# ETAG_v10_0_EM4095.net
KiCad netlist of a schematic drawn in EAGLE
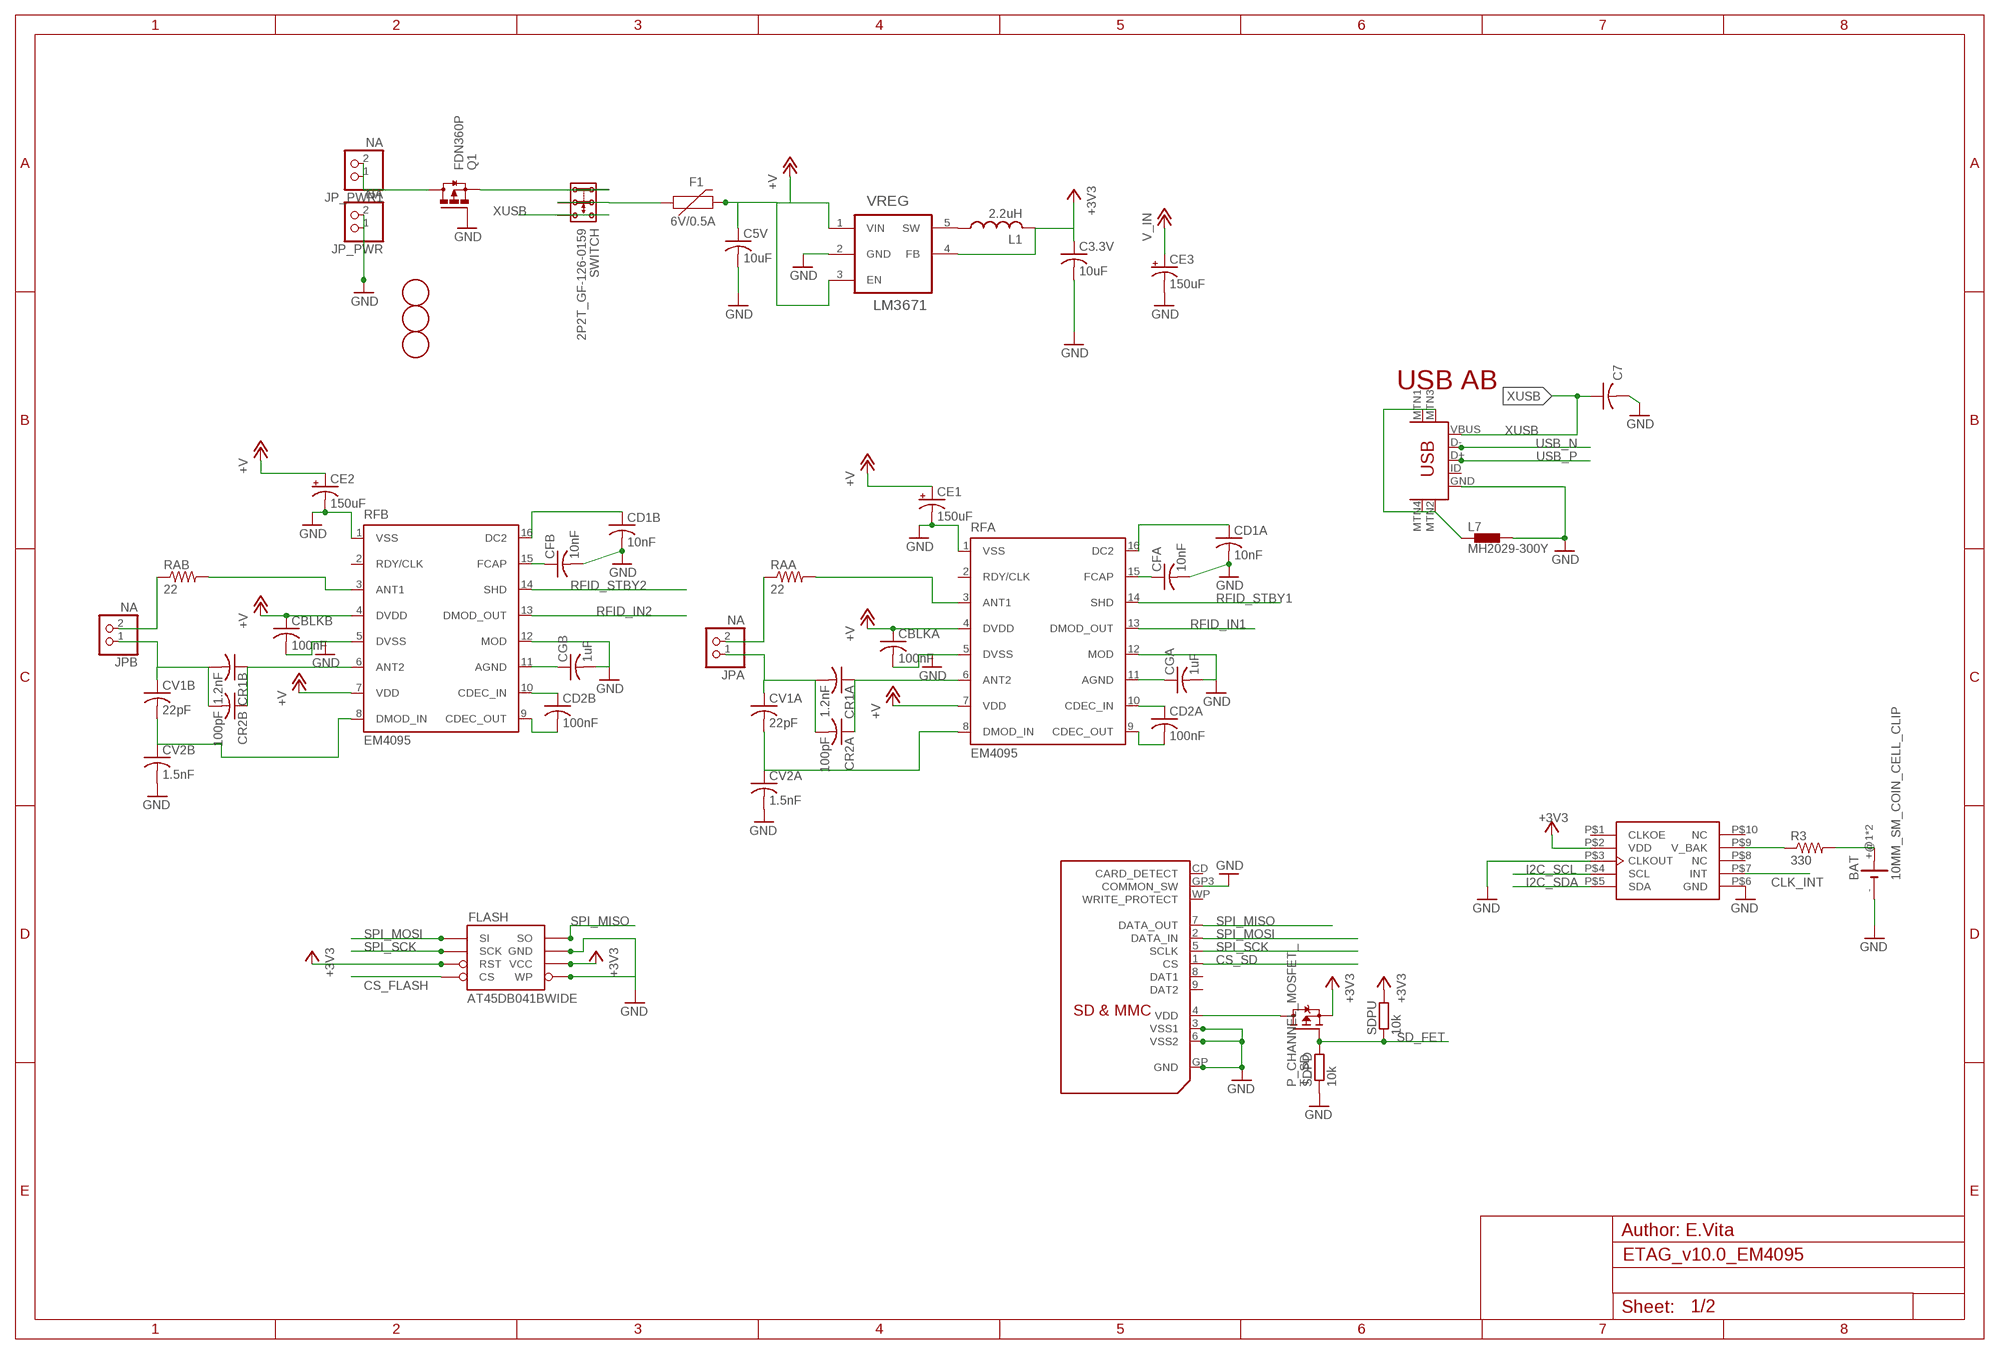
[diagram p0: schematic, sheet 1]
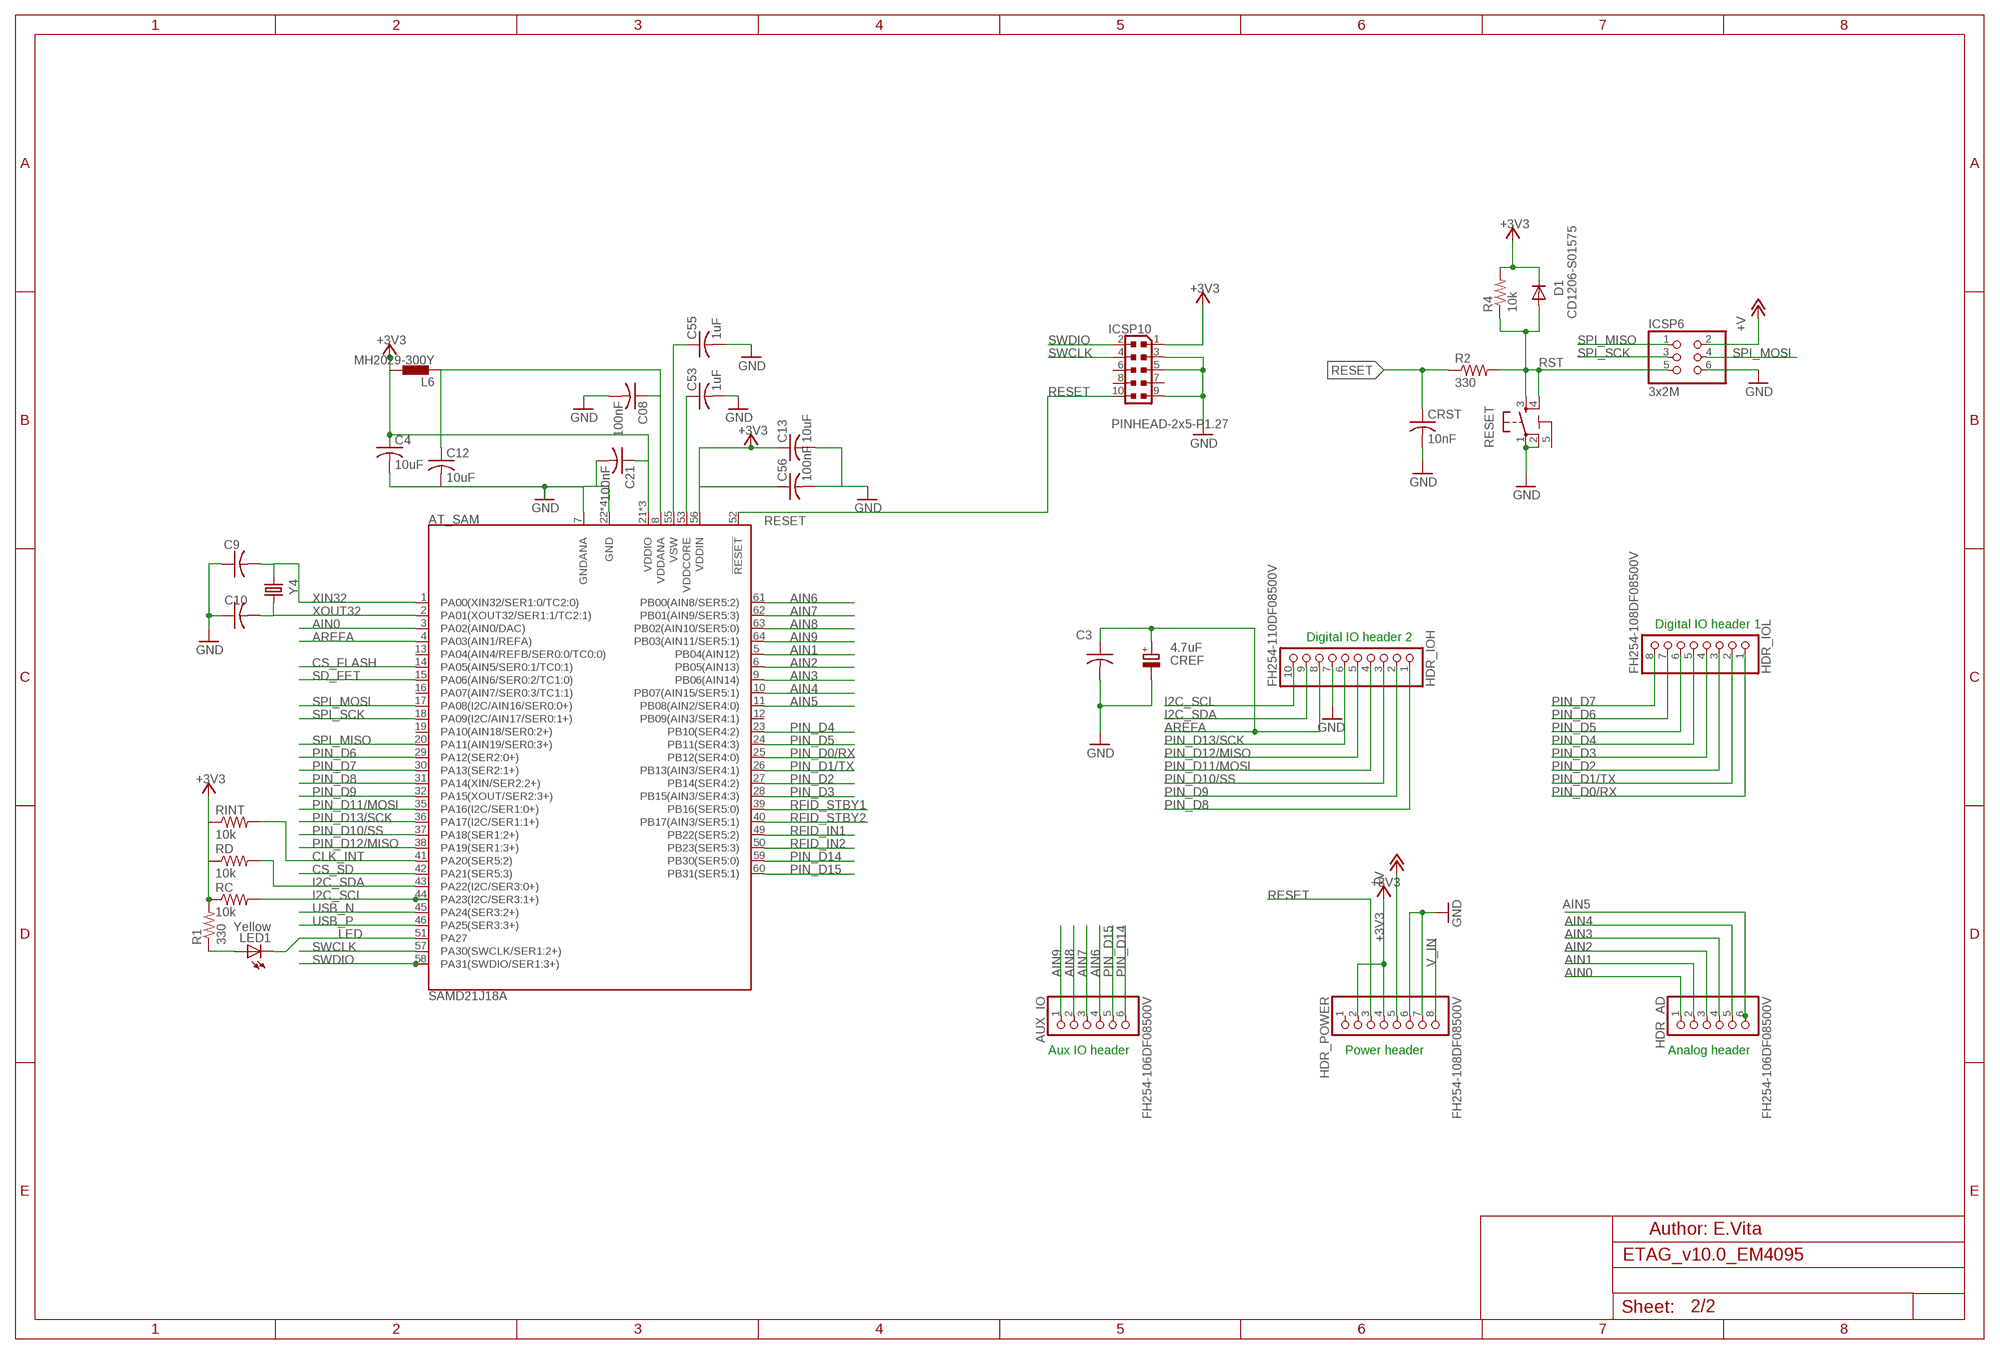
[diagram p1: schematic, sheet 2]

(export (version "E")
  (design (tool "Eeschema 10.0.6"))
  (components
    (comp (ref "BAT")
      (value "10MM_SM_COIN_CELL_CLIP")
      (footprint "eagle-import:10MM_SM_COIN_CELL_CLIP")
      (libsource (lib "eagle-import") (part "10MM_SM_COIN_CELL_CLIP"))
    )
    (comp (ref "C3.3V")
      (value "10uF")
      (footprint "eagle-import:C0805")
      (libsource (lib "eagle-import") (part "C-USC0805"))
    )
    (comp (ref "C5V")
      (value "10uF")
      (footprint "eagle-import:C0805")
      (libsource (lib "eagle-import") (part "C-USC0805"))
    )
    (comp (ref "C7")
      (value "10nF")
      (footprint "eagle-import:C0603-ROUND")
      (libsource (lib "eagle-import") (part "C-USROUND"))
    )
    (comp (ref "CBLKA")
      (value "100nF")
      (footprint "eagle-import:C0603-ROUND")
      (libsource (lib "eagle-import") (part "C-US"))
    )
    (comp (ref "CBLKB")
      (value "100nF")
      (footprint "eagle-import:C0603-ROUND")
      (libsource (lib "eagle-import") (part "C-US"))
    )
    (comp (ref "CD1A")
      (value "10nF")
      (footprint "eagle-import:C0603-ROUND")
      (libsource (lib "eagle-import") (part "C-US"))
    )
    (comp (ref "CD1B")
      (value "10nF")
      (footprint "eagle-import:C0603-ROUND")
      (libsource (lib "eagle-import") (part "C-USROUND"))
    )
    (comp (ref "CD2A")
      (value "100nF")
      (footprint "eagle-import:C0603-ROUND")
      (libsource (lib "eagle-import") (part "C-US"))
    )
    (comp (ref "CD2B")
      (value "100nF")
      (footprint "eagle-import:C0603-ROUND")
      (libsource (lib "eagle-import") (part "C-US"))
    )
    (comp (ref "CE1")
      (value "150uF")
      (footprint "eagle-import:E2-5")
      (libsource (lib "eagle-import") (part "CPOL-USE2-5"))
    )
    (comp (ref "CE2")
      (value "150uF")
      (footprint "eagle-import:E2-5")
      (libsource (lib "eagle-import") (part "CPOL-USE2-5"))
    )
    (comp (ref "CE3")
      (value "150uF")
      (footprint "eagle-import:E2-5")
      (libsource (lib "eagle-import") (part "CPOL-USE2-5"))
    )
    (comp (ref "CFA")
      (value "10nF")
      (footprint "eagle-import:C0603-ROUND")
      (libsource (lib "eagle-import") (part "C-USROUND"))
    )
    (comp (ref "CFB")
      (value "10nF")
      (footprint "eagle-import:C0603-ROUND")
      (libsource (lib "eagle-import") (part "C-US"))
    )
    (comp (ref "CGA")
      (value "1uF")
      (footprint "eagle-import:C0603-ROUND")
      (libsource (lib "eagle-import") (part "C-US"))
    )
    (comp (ref "CGB")
      (value "1uF")
      (footprint "eagle-import:C0603-ROUND")
      (libsource (lib "eagle-import") (part "C-US"))
    )
    (comp (ref "CR1A")
      (value "1.2nF")
      (footprint "eagle-import:C0603-ROUND")
      (libsource (lib "eagle-import") (part "C-USROUND"))
    )
    (comp (ref "CR1B")
      (value "1.2nF")
      (footprint "eagle-import:C0603-ROUND")
      (libsource (lib "eagle-import") (part "C-US"))
    )
    (comp (ref "CR2A")
      (value "100pF")
      (footprint "eagle-import:C0603-ROUND")
      (libsource (lib "eagle-import") (part "C-US"))
    )
    (comp (ref "CR2B")
      (value "100pF")
      (footprint "eagle-import:C0603-ROUND")
      (libsource (lib "eagle-import") (part "C-US"))
    )
    (comp (ref "CV1A")
      (value "22pF")
      (footprint "eagle-import:C0603-ROUND")
      (libsource (lib "eagle-import") (part "C-US"))
    )
    (comp (ref "CV1B")
      (value "22pF")
      (footprint "eagle-import:C0603-ROUND")
      (libsource (lib "eagle-import") (part "C-US"))
    )
    (comp (ref "CV2A")
      (value "1.5nF")
      (footprint "eagle-import:C0603-ROUND")
      (libsource (lib "eagle-import") (part "C-USROUND"))
    )
    (comp (ref "CV2B")
      (value "1.5nF")
      (footprint "eagle-import:C0603-ROUND")
      (libsource (lib "eagle-import") (part "C-US"))
    )
    (comp (ref "F1")
      (value "6V/0.5A")
      (footprint "eagle-import:1206")
      (libsource (lib "eagle-import") (part "PPTC_6V500MA-2"))
    )
    (comp (ref "FD1")
      (value "FIDUCIALMOUNT")
      (footprint "eagle-import:FIDUCIA-MOUNT")
      (libsource (lib "eagle-import") (part "FIDUCIALMOUNT"))
    )
    (comp (ref "FD2")
      (value "FIDUCIALMOUNT")
      (footprint "eagle-import:FIDUCIA-MOUNT")
      (libsource (lib "eagle-import") (part "FIDUCIALMOUNT"))
    )
    (comp (ref "FD3")
      (value "FIDUCIALMOUNT")
      (footprint "eagle-import:FIDUCIA-MOUNT")
      (libsource (lib "eagle-import") (part "FIDUCIALMOUNT"))
    )
    (comp (ref "FLASH")
      (value "AT45DB041BWIDE")
      (footprint "eagle-import:SO08WIDE")
      (libsource (lib "eagle-import") (part "AT45DB041BWIDE"))
    )
    (comp (ref "JPA")
      (value "NA")
      (footprint "eagle-import:1X02")
      (libsource (lib "eagle-import") (part "PINHD-1X2"))
    )
    (comp (ref "JPB")
      (value "NA")
      (footprint "eagle-import:1X02")
      (libsource (lib "eagle-import") (part "PINHD-1X2"))
    )
    (comp (ref "JP_PWR")
      (value "NA")
      (footprint "eagle-import:1X02")
      (libsource (lib "eagle-import") (part "PINHD-1X2"))
    )
    (comp (ref "JP_PWR1")
      (value "NA")
      (footprint "eagle-import:1X02")
      (libsource (lib "eagle-import") (part "PINHD-1X2"))
    )
    (comp (ref "L1")
      (value "2.2uH")
      (footprint "eagle-import:SMT_COIL_INDUCTOR_4X4MM")
      (libsource (lib "eagle-import") (part "L-US4X4"))
    )
    (comp (ref "L7")
      (value "MH2029-300Y")
      (footprint "eagle-import:C0805K")
      (libsource (lib "eagle-import") (part "BLM15H0805"))
    )
    (comp (ref "Q1")
      (value "FDN360P")
      (footprint "eagle-import:SUPER-SOT3")
      (libsource (lib "eagle-import") (part "FDN360P"))
    )
    (comp (ref "R3")
      (value "330")
      (footprint "eagle-import:C0603-ROUND")
      (libsource (lib "eagle-import") (part "R-US_ROUND"))
    )
    (comp (ref "RAA")
      (value "22")
      (footprint "eagle-import:R0805")
      (libsource (lib "eagle-import") (part "R-US_R0805"))
    )
    (comp (ref "RAB")
      (value "22")
      (footprint "eagle-import:R0805")
      (libsource (lib "eagle-import") (part "R-US_R0805"))
    )
    (comp (ref "RFA")
      (value "EM4095")
      (footprint "eagle-import:SO16")
      (libsource (lib "eagle-import") (part "EM4095"))
    )
    (comp (ref "RFB")
      (value "EM4095")
      (footprint "eagle-import:SO16")
      (libsource (lib "eagle-import") (part "EM4095"))
    )
    (comp (ref "RTC")
      (value "MC-RTC-RV-3029-C3-I2C")
      (footprint "eagle-import:MC-RTC-C3_SPECIAL")
      (libsource (lib "eagle-import") (part "MC-RTC-RV-3029-C3-I2C"))
    )
    (comp (ref "SD")
      (value "SDMMC06132")
      (footprint "eagle-import:06132")
      (libsource (lib "eagle-import") (part "SDMMC06132"))
    )
    (comp (ref "SDPD")
      (value "10k")
      (footprint "eagle-import:R0603-ROUND")
      (fields (field (name "PART_NUMBER") "CR0603JW103L"))
      (libsource (lib "eagle-import") (part "0028_CR0603JW103L"))
    )
    (comp (ref "SDPU")
      (value "10k")
      (footprint "eagle-import:R0603-ROUND")
      (fields (field (name "PART_NUMBER") "CR0603JW103L"))
      (libsource (lib "eagle-import") (part "0028_CR0603JW103L"))
    )
    (comp (ref "SWITCH")
      (value "2P2T_GF-126-0159")
      (footprint "eagle-import:2P2T_GF-126-0159")
      (libsource (lib "eagle-import") (part "2P2T_GF-126-0159"))
    )
    (comp (ref "T_SD")
      (value "P_CHANNEL_MOSFET_")
      (footprint "eagle-import:SOT23")
      (libsource (lib "eagle-import") (part "P_CHANNEL_MOSFET_"))
    )
    (comp (ref "USB")
      (value "USB-MINIB-5PIN")
      (footprint "eagle-import:USB-MINIB")
      (libsource (lib "eagle-import") (part "USB-MINIB-5PIN"))
    )
    (comp (ref "VREG")
      (value "LM3671")
      (footprint "eagle-import:SOT23-5L")
      (libsource (lib "eagle-import") (part "LM3671_SWITCHING_REGSOT23"))
    )
    (comp (ref "AT_SAM")
      (value "SAMD21J18A")
      (footprint "eagle-import:TQFP_10MM_0.5PITCH")
      (libsource (lib "eagle-import") (part "ATSAML21JTQFP_10MM_0.5PITCH"))
    )
    (comp (ref "AUX_IO")
      (value "FH254-106DF08500V")
      (footprint "eagle-import:1X06")
      (fields (field (name "PART_NUMBER") "20TW-535"))
      (libsource (lib "eagle-import") (part "1682_20TW-535_STD"))
    )
    (comp (ref "C3")
      (value "100nF")
      (footprint "eagle-import:C0603-ROUND")
      (libsource (lib "eagle-import") (part "C-USROUND"))
    )
    (comp (ref "C4")
      (value "10uF")
      (footprint "eagle-import:C0805")
      (libsource (lib "eagle-import") (part "C-USC0805"))
    )
    (comp (ref "C08")
      (value "100nF")
      (footprint "eagle-import:C0603-ROUND")
      (libsource (lib "eagle-import") (part "C-USROUND"))
    )
    (comp (ref "C9")
      (value "22pF")
      (footprint "eagle-import:C0603-ROUND")
      (libsource (lib "eagle-import") (part "C-USROUND"))
    )
    (comp (ref "C10")
      (value "22pF")
      (footprint "eagle-import:C0603-ROUND")
      (libsource (lib "eagle-import") (part "C-USROUND"))
    )
    (comp (ref "C12")
      (value "10uF")
      (footprint "eagle-import:C0805")
      (libsource (lib "eagle-import") (part "C-USC0805"))
    )
    (comp (ref "C13")
      (value "10uF")
      (footprint "eagle-import:C0805")
      (libsource (lib "eagle-import") (part "C-USC0805"))
    )
    (comp (ref "C21")
      (value "100nF")
      (footprint "eagle-import:C0603-ROUND")
      (libsource (lib "eagle-import") (part "C-USROUND"))
    )
    (comp (ref "C53")
      (value "1uF")
      (footprint "eagle-import:C0603-ROUND")
      (libsource (lib "eagle-import") (part "C-USROUND"))
    )
    (comp (ref "C55")
      (value "1uF")
      (footprint "eagle-import:C0603-ROUND")
      (libsource (lib "eagle-import") (part "C-USROUND"))
    )
    (comp (ref "C56")
      (value "100nF")
      (footprint "eagle-import:C0603-ROUND")
      (libsource (lib "eagle-import") (part "C-USROUND"))
    )
    (comp (ref "CREF")
      (value "4.7uF")
      (footprint "eagle-import:SMC_A")
      (fields (field (name "PART_NUMBER") "TAJA475M016RNJ"))
      (libsource (lib "eagle-import") (part "0474_TAJA475M016RNJ"))
    )
    (comp (ref "CRST")
      (value "10nF")
      (footprint "eagle-import:C0603-ROUND")
      (libsource (lib "eagle-import") (part "C-USROUND"))
    )
    (comp (ref "D1")
      (value "CD1206-S01575")
      (footprint "eagle-import:MINIMELF")
      (libsource (lib "eagle-import") (part "0012_CD1206-S01575"))
    )
    (comp (ref "HDR_AD")
      (value "FH254-106DF08500V")
      (footprint "eagle-import:1X06")
      (fields (field (name "PART_NUMBER") "20TW-535"))
      (libsource (lib "eagle-import") (part "1682_20TW-535_STD"))
    )
    (comp (ref "HDR_IOH")
      (value "FH254-110DF08500V")
      (footprint "eagle-import:1X10")
      (fields (field (name "PART_NUMBER") "20TW-537"))
      (libsource (lib "eagle-import") (part "1684_20TW-537"))
    )
    (comp (ref "HDR_IOL")
      (value "FH254-108DF08500V")
      (footprint "eagle-import:1X08")
      (fields (field (name "PART_NUMBER") "20TW-536"))
      (libsource (lib "eagle-import") (part "1683_20TW-536"))
    )
    (comp (ref "HDR_POWER")
      (value "FH254-108DF08500V")
      (footprint "eagle-import:1X08")
      (fields (field (name "PART_NUMBER") "20TW-536"))
      (libsource (lib "eagle-import") (part "1683_20TW-536"))
    )
    (comp (ref "ICSP6")
      (value "3x2M")
      (footprint "eagle-import:2X03")
      (fields (field (name "PART_NUMBER") "PH254-203DF118A00V"))
      (libsource (lib "eagle-import") (part "0114_PH254-203DF118A00V"))
    )
    (comp (ref "ICSP10")
      (value "PINHEAD-2x5-P1.27")
      (footprint "eagle-import:PINHEAD_2X05_127")
      (libsource (lib "eagle-import") (part "0171_PH127-205DF055G00AROUND-PADS"))
    )
    (comp (ref "L6")
      (value "MH2029-300Y")
      (footprint "eagle-import:C0805K")
      (libsource (lib "eagle-import") (part "BLM15H0805"))
    )
    (comp (ref "LED1")
      (value "Yellow")
      (footprint "eagle-import:CHIPLED_0805")
      (fields (field (name "PART_NUMBER") "KPT-2012YC"))
      (libsource (lib "eagle-import") (part "0044_KPT-2012YC"))
    )
    (comp (ref "R1")
      (value "330")
      (footprint "eagle-import:C0603-ROUND")
      (libsource (lib "eagle-import") (part "R-US_ROUND"))
    )
    (comp (ref "R2")
      (value "330")
      (footprint "eagle-import:C0603-ROUND")
      (libsource (lib "eagle-import") (part "R-US_ROUND"))
    )
    (comp (ref "R4")
      (value "10k")
      (footprint "eagle-import:C0603-ROUND")
      (libsource (lib "eagle-import") (part "R-US_ROUND"))
    )
    (comp (ref "RC")
      (value "10k")
      (footprint "eagle-import:C0603-ROUND")
      (libsource (lib "eagle-import") (part "R-US_ROUND"))
    )
    (comp (ref "RD")
      (value "10k")
      (footprint "eagle-import:C0603-ROUND")
      (libsource (lib "eagle-import") (part "R-US_ROUND"))
    )
    (comp (ref "RESET")
      (value "TS42031-160R-TR-7260")
      (footprint "eagle-import:TS42")
      (fields (field (name "PART_NUMBER") "IT-1157AHNP-160G-G_GTR"))
      (libsource (lib "eagle-import") (part "0946_TS42031-160W-TR-7260"))
    )
    (comp (ref "RINT")
      (value "10k")
      (footprint "eagle-import:C0603-ROUND")
      (libsource (lib "eagle-import") (part "R-US_ROUND"))
    )
    (comp (ref "Y4")
      (value "32,768Khz")
      (footprint "eagle-import:RESONATOR_EPSON_FC_145")
      (fields (field (name "PART_NUMBER") "ABS07-32.768KHZ-T"))
      (libsource (lib "eagle-import") (part "0213_ABS07-32.768KHZ-T"))
    )
  )
  (nets
    (net (code "1") (name "+3V3") (class "Default")
      (node (ref "AT_SAM") (pin "21") (pinfunction "VDDIO_21") (pintype "bidirectional"))
      (node (ref "AT_SAM") (pin "34") (pinfunction "VDDIO_34") (pintype "bidirectional"))
      (node (ref "AT_SAM") (pin "48") (pinfunction "VDDIO_48") (pintype "bidirectional"))
      (node (ref "AT_SAM") (pin "56") (pinfunction "VDDIN_56") (pintype "bidirectional"))
      (node (ref "C13") (pin "1") (pinfunction "1_1") (pintype "passive"))
      (node (ref "C21") (pin "1") (pinfunction "1_1") (pintype "passive"))
      (node (ref "C3.3V") (pin "1") (pinfunction "1_1") (pintype "passive"))
      (node (ref "C4") (pin "1") (pinfunction "1_1") (pintype "passive"))
      (node (ref "C56") (pin "1") (pinfunction "1_1") (pintype "passive"))
      (node (ref "D1") (pin "C") (pinfunction "C_C") (pintype "passive"))
      (node (ref "FLASH") (pin "3") (pinfunction "RST_3") (pintype "bidirectional"))
      (node (ref "FLASH") (pin "6") (pinfunction "VCC_6") (pintype "bidirectional"))
      (node (ref "HDR_POWER") (pin "2") (pinfunction "2_2") (pintype "passive"))
      (node (ref "HDR_POWER") (pin "4") (pinfunction "4_4") (pintype "passive"))
      (node (ref "ICSP10") (pin "1") (pinfunction "1_1") (pintype "passive"))
      (node (ref "L1") (pin "P$2") (pinfunction "2_P$2") (pintype "passive"))
      (node (ref "L6") (pin "2") (pinfunction "2_2") (pintype "passive"))
      (node (ref "R1") (pin "2") (pinfunction "2_2") (pintype "passive"))
      (node (ref "R4") (pin "2") (pinfunction "2_2") (pintype "passive"))
      (node (ref "RC") (pin "1") (pinfunction "1_1") (pintype "passive"))
      (node (ref "RD") (pin "1") (pinfunction "1_1") (pintype "passive"))
      (node (ref "RINT") (pin "1") (pinfunction "1_1") (pintype "passive"))
      (node (ref "RTC") (pin "P$2") (pinfunction "VDD_P$2") (pintype "power_in"))
      (node (ref "SDPU") (pin "2") (pinfunction "2_2") (pintype "passive"))
      (node (ref "T_SD") (pin "2") (pinfunction "S_2") (pintype "passive"))
      (node (ref "VREG") (pin "4") (pinfunction "FB_4") (pintype "power_in"))
    )
    (net (code "2") (name "5-GND") (class "Default")
      (node (ref "RESET") (pin "5") (pinfunction "5-GND_5") (pintype "power_in"))
    )
    (net (code "3") (name "AIN0") (class "Default")
      (node (ref "AT_SAM") (pin "3") (pinfunction "PA02(AIN0/DAC)_3") (pintype "bidirectional"))
      (node (ref "HDR_AD") (pin "1") (pinfunction "1_1") (pintype "passive"))
    )
    (net (code "4") (name "AIN1") (class "Default")
      (node (ref "AT_SAM") (pin "5") (pinfunction "PB04(AIN12)_5") (pintype "bidirectional"))
      (node (ref "HDR_AD") (pin "2") (pinfunction "2_2") (pintype "passive"))
    )
    (net (code "5") (name "AIN2") (class "Default")
      (node (ref "AT_SAM") (pin "6") (pinfunction "PB05(AIN13)_6") (pintype "bidirectional"))
      (node (ref "HDR_AD") (pin "3") (pinfunction "3_3") (pintype "passive"))
    )
    (net (code "6") (name "AIN3") (class "Default")
      (node (ref "AT_SAM") (pin "9") (pinfunction "PB06(AIN14)_9") (pintype "bidirectional"))
      (node (ref "HDR_AD") (pin "4") (pinfunction "4_4") (pintype "passive"))
    )
    (net (code "7") (name "AIN4") (class "Default")
      (node (ref "AT_SAM") (pin "10") (pinfunction "PB07(AIN15/SER5:1)_10") (pintype "bidirectional"))
      (node (ref "HDR_AD") (pin "5") (pinfunction "5_5") (pintype "passive"))
    )
    (net (code "8") (name "AIN5") (class "Default")
      (node (ref "AT_SAM") (pin "11") (pinfunction "PB08(AIN2/SER4:0)_11") (pintype "bidirectional"))
      (node (ref "HDR_AD") (pin "6") (pinfunction "6_6") (pintype "passive"))
    )
    (net (code "9") (name "AIN6") (class "Default")
      (node (ref "AT_SAM") (pin "61") (pinfunction "PB00(AIN8/SER5:2)_61") (pintype "bidirectional"))
      (node (ref "AUX_IO") (pin "4") (pinfunction "4_4") (pintype "passive"))
    )
    (net (code "10") (name "AIN7") (class "Default")
      (node (ref "AT_SAM") (pin "62") (pinfunction "PB01(AIN9/SER5:3)_62") (pintype "bidirectional"))
      (node (ref "AUX_IO") (pin "3") (pinfunction "3_3") (pintype "passive"))
    )
    (net (code "11") (name "AIN8") (class "Default")
      (node (ref "AT_SAM") (pin "63") (pinfunction "PB02(AIN10/SER5:0)_63") (pintype "bidirectional"))
      (node (ref "AUX_IO") (pin "2") (pinfunction "2_2") (pintype "passive"))
    )
    (net (code "12") (name "AIN9") (class "Default")
      (node (ref "AT_SAM") (pin "64") (pinfunction "PB03(AIN11/SER5:1)_64") (pintype "bidirectional"))
      (node (ref "AUX_IO") (pin "1") (pinfunction "1_1") (pintype "passive"))
    )
    (net (code "13") (name "AREFA") (class "Default")
      (node (ref "AT_SAM") (pin "4") (pinfunction "PA03(AIN1/REFA)_4") (pintype "bidirectional"))
      (node (ref "C3") (pin "1") (pinfunction "1_1") (pintype "passive"))
      (node (ref "CREF") (pin "+") (pinfunction "+_+") (pintype "passive"))
      (node (ref "HDR_IOH") (pin "8") (pinfunction "8_8") (pintype "passive"))
    )
    (net (code "14") (name "CLK_INT") (class "Default")
      (node (ref "AT_SAM") (pin "41") (pinfunction "PA20(SER5:2)_41") (pintype "bidirectional"))
      (node (ref "RINT") (pin "2") (pinfunction "2_2") (pintype "passive"))
      (node (ref "RTC") (pin "P$7") (pinfunction "INT_P$7") (pintype "bidirectional"))
    )
    (net (code "15") (name "CS_FLASH") (class "Default")
      (node (ref "AT_SAM") (pin "14") (pinfunction "PA05(AIN5/SER0:1/TC0:1)_14") (pintype "bidirectional"))
      (node (ref "FLASH") (pin "4") (pinfunction "CS_4") (pintype "bidirectional"))
    )
    (net (code "16") (name "CS_SD") (class "Default")
      (node (ref "AT_SAM") (pin "42") (pinfunction "PA21(SER5:3)_42") (pintype "bidirectional"))
      (node (ref "SD") (pin "1") (pinfunction "CS_1") (pintype "input"))
    )
    (net (code "17") (name "GND") (class "Default")
      (node (ref "AT_SAM") (pin "22") (pinfunction "GND_22") (pintype "bidirectional"))
      (node (ref "AT_SAM") (pin "33") (pinfunction "GND_33") (pintype "bidirectional"))
      (node (ref "AT_SAM") (pin "47") (pinfunction "GND_47") (pintype "bidirectional"))
      (node (ref "AT_SAM") (pin "54") (pinfunction "GND_54") (pintype "bidirectional"))
      (node (ref "AT_SAM") (pin "7") (pinfunction "GNDANA_7") (pintype "bidirectional"))
      (node (ref "BAT") (pin "-") (pinfunction "-_-") (pintype "passive"))
      (node (ref "C08") (pin "2") (pinfunction "2_2") (pintype "passive"))
      (node (ref "C10") (pin "1") (pinfunction "1_1") (pintype "passive"))
      (node (ref "C12") (pin "2") (pinfunction "2_2") (pintype "passive"))
      (node (ref "C13") (pin "2") (pinfunction "2_2") (pintype "passive"))
      (node (ref "C21") (pin "2") (pinfunction "2_2") (pintype "passive"))
      (node (ref "C3") (pin "2") (pinfunction "2_2") (pintype "passive"))
      (node (ref "C3.3V") (pin "2") (pinfunction "2_2") (pintype "passive"))
      (node (ref "C4") (pin "2") (pinfunction "2_2") (pintype "passive"))
      (node (ref "C53") (pin "2") (pinfunction "2_2") (pintype "passive"))
      (node (ref "C55") (pin "2") (pinfunction "2_2") (pintype "passive"))
      (node (ref "C56") (pin "2") (pinfunction "2_2") (pintype "passive"))
      (node (ref "C5V") (pin "2") (pinfunction "2_2") (pintype "passive"))
      (node (ref "C7") (pin "2") (pinfunction "2_2") (pintype "passive"))
      (node (ref "C9") (pin "1") (pinfunction "1_1") (pintype "passive"))
      (node (ref "CBLKA") (pin "2") (pinfunction "2_2") (pintype "passive"))
      (node (ref "CBLKB") (pin "2") (pinfunction "2_2") (pintype "passive"))
      (node (ref "CD1A") (pin "2") (pinfunction "2_2") (pintype "passive"))
      (node (ref "CD1B") (pin "2") (pinfunction "2_2") (pintype "passive"))
      (node (ref "CE1") (pin "-") (pinfunction "-_-") (pintype "passive"))
      (node (ref "CE2") (pin "-") (pinfunction "-_-") (pintype "passive"))
      (node (ref "CE3") (pin "-") (pinfunction "-_-") (pintype "passive"))
      (node (ref "CFA") (pin "2") (pinfunction "2_2") (pintype "passive"))
      (node (ref "CFB") (pin "2") (pinfunction "2_2") (pintype "passive"))
      (node (ref "CGA") (pin "2") (pinfunction "2_2") (pintype "passive"))
      (node (ref "CGB") (pin "2") (pinfunction "2_2") (pintype "passive"))
      (node (ref "CREF") (pin "-") (pinfunction "-_-") (pintype "passive"))
      (node (ref "CRST") (pin "2") (pinfunction "2_2") (pintype "passive"))
      (node (ref "CV2A") (pin "2") (pinfunction "2_2") (pintype "passive"))
      (node (ref "CV2B") (pin "2") (pinfunction "2_2") (pintype "passive"))
      (node (ref "FLASH") (pin "5") (pinfunction "WP_5") (pintype "bidirectional"))
      (node (ref "FLASH") (pin "7") (pinfunction "GND_7") (pintype "bidirectional"))
      (node (ref "HDR_IOH") (pin "7") (pinfunction "7_7") (pintype "passive"))
      (node (ref "HDR_POWER") (pin "6") (pinfunction "6_6") (pintype "passive"))
      (node (ref "HDR_POWER") (pin "7") (pinfunction "7_7") (pintype "passive"))
      (node (ref "ICSP10") (pin "3") (pinfunction "3_3") (pintype "passive"))
      (node (ref "ICSP10") (pin "5") (pinfunction "5_5") (pintype "passive"))
      (node (ref "ICSP10") (pin "9") (pinfunction "9_9") (pintype "passive"))
      (node (ref "ICSP6") (pin "6") (pinfunction "6_6") (pintype "passive"))
      (node (ref "JP_PWR") (pin "1") (pinfunction "1_1") (pintype "passive"))
      (node (ref "JP_PWR") (pin "2") (pinfunction "2_2") (pintype "passive"))
      (node (ref "L7") (pin "2") (pinfunction "2_2") (pintype "passive"))
      (node (ref "Q1") (pin "1") (pinfunction "G_1") (pintype "passive"))
      (node (ref "RESET") (pin "1") (pinfunction "1_1") (pintype "passive"))
      (node (ref "RESET") (pin "2") (pinfunction "2_2") (pintype "passive"))
      (node (ref "RFA") (pin "1") (pinfunction "VSS_1") (pintype "power_in"))
      (node (ref "RFA") (pin "12") (pinfunction "MOD_12") (pintype "input"))
      (node (ref "RFA") (pin "5") (pinfunction "DVSS_5") (pintype "power_in"))
      (node (ref "RFB") (pin "1") (pinfunction "VSS_1") (pintype "power_in"))
      (node (ref "RFB") (pin "12") (pinfunction "MOD_12") (pintype "input"))
      (node (ref "RFB") (pin "5") (pinfunction "DVSS_5") (pintype "power_in"))
      (node (ref "RTC") (pin "P$3") (pinfunction "CLKOUT_P$3") (pintype "output"))
      (node (ref "RTC") (pin "P$6") (pinfunction "GND_P$6") (pintype "power_in"))
      (node (ref "SD") (pin "3") (pinfunction "VSS1_3") (pintype "power_in"))
      (node (ref "SD") (pin "6") (pinfunction "VSS2_6") (pintype "power_in"))
      (node (ref "SD") (pin "GP") (pinfunction "GND_GP") (pintype "power_in"))
      (node (ref "SD") (pin "GP3") (pinfunction "COMMON_SW_GP3") (pintype "passive"))
      (node (ref "SDPD") (pin "1") (pinfunction "1_1") (pintype "passive"))
      (node (ref "USB") (pin "GND") (pinfunction "GND_GND") (pintype "bidirectional"))
      (node (ref "VREG") (pin "2") (pinfunction "GND_2") (pintype "passive"))
    )
    (net (code "18") (name "I2C_SCL") (class "Default")
      (node (ref "AT_SAM") (pin "44") (pinfunction "PA23(I2C/SER3:1+)_44") (pintype "bidirectional"))
      (node (ref "HDR_IOH") (pin "10") (pinfunction "10_10") (pintype "passive"))
      (node (ref "RC") (pin "2") (pinfunction "2_2") (pintype "passive"))
      (node (ref "RTC") (pin "P$4") (pinfunction "SCL_P$4") (pintype "bidirectional"))
    )
    (net (code "19") (name "I2C_SDA") (class "Default")
      (node (ref "AT_SAM") (pin "43") (pinfunction "PA22(I2C/SER3:0+)_43") (pintype "bidirectional"))
      (node (ref "HDR_IOH") (pin "9") (pinfunction "9_9") (pintype "passive"))
      (node (ref "RD") (pin "2") (pinfunction "2_2") (pintype "passive"))
      (node (ref "RTC") (pin "P$5") (pinfunction "SDA_P$5") (pintype "bidirectional"))
    )
    (net (code "20") (name "LED") (class "Default")
      (node (ref "AT_SAM") (pin "51") (pinfunction "PA27_51") (pintype "bidirectional"))
      (node (ref "LED1") (pin "C") (pinfunction "C_C") (pintype "passive"))
    )
    (net (code "21") (name "Net-(AT_SAM-VDDANA)") (class "Default")
      (node (ref "AT_SAM") (pin "8") (pinfunction "VDDANA_8") (pintype "bidirectional"))
      (node (ref "C08") (pin "1") (pinfunction "1_1") (pintype "passive"))
      (node (ref "C12") (pin "1") (pinfunction "1_1") (pintype "passive"))
      (node (ref "L6") (pin "1") (pinfunction "1_1") (pintype "passive"))
    )
    (net (code "22") (name "Net-(AT_SAM-VDDCORE)") (class "Default")
      (node (ref "AT_SAM") (pin "53") (pinfunction "VDDCORE_53") (pintype "bidirectional"))
      (node (ref "C53") (pin "1") (pinfunction "1_1") (pintype "passive"))
    )
    (net (code "23") (name "Net-(AT_SAM-VSW)") (class "Default")
      (node (ref "AT_SAM") (pin "55") (pinfunction "VSW_55") (pintype "bidirectional"))
      (node (ref "C55") (pin "1") (pinfunction "1_1") (pintype "passive"))
    )
    (net (code "24") (name "Net-(BAT-+-Pad+@1)") (class "Default")
      (node (ref "BAT") (pin "+@1") (pinfunction "+_+@1") (pintype "passive"))
      (node (ref "BAT") (pin "+@2") (pinfunction "+_+@2") (pintype "passive"))
      (node (ref "R3") (pin "2") (pinfunction "2_2") (pintype "passive"))
    )
    (net (code "25") (name "Net-(CR1A-Pad2)") (class "Default")
      (node (ref "CR1A") (pin "2") (pinfunction "2_2") (pintype "passive"))
      (node (ref "CR2A") (pin "2") (pinfunction "2_2") (pintype "passive"))
      (node (ref "CV1A") (pin "1") (pinfunction "1_1") (pintype "passive"))
      (node (ref "JPA") (pin "1") (pinfunction "1_1") (pintype "passive"))
    )
    (net (code "26") (name "Net-(CR1B-Pad2)") (class "Default")
      (node (ref "CR1B") (pin "2") (pinfunction "2_2") (pintype "passive"))
      (node (ref "CR2B") (pin "2") (pinfunction "2_2") (pintype "passive"))
      (node (ref "CV1B") (pin "1") (pinfunction "1_1") (pintype "passive"))
      (node (ref "JPB") (pin "1") (pinfunction "1_1") (pintype "passive"))
    )
    (net (code "27") (name "Net-(JPA-Pad2)") (class "Default")
      (node (ref "JPA") (pin "2") (pinfunction "2_2") (pintype "passive"))
      (node (ref "RAA") (pin "1") (pinfunction "1_1") (pintype "passive"))
    )
    (net (code "28") (name "Net-(JPB-Pad2)") (class "Default")
      (node (ref "JPB") (pin "2") (pinfunction "2_2") (pintype "passive"))
      (node (ref "RAB") (pin "1") (pinfunction "1_1") (pintype "passive"))
    )
    (net (code "29") (name "Net-(L1-1)") (class "Default")
      (node (ref "L1") (pin "P$1") (pinfunction "1_P$1") (pintype "passive"))
      (node (ref "VREG") (pin "5") (pinfunction "SW_5") (pintype "power_in"))
    )
    (net (code "30") (name "Net-(LED1-PadA)") (class "Default")
      (node (ref "LED1") (pin "A") (pinfunction "A_A") (pintype "passive"))
      (node (ref "R1") (pin "1") (pinfunction "1_1") (pintype "passive"))
    )
    (net (code "31") (name "Net-(Q1-D)") (class "Default")
      (node (ref "JP_PWR1") (pin "1") (pinfunction "1_1") (pintype "passive"))
      (node (ref "JP_PWR1") (pin "2") (pinfunction "2_2") (pintype "passive"))
      (node (ref "Q1") (pin "3") (pinfunction "D_3") (pintype "passive"))
    )
    (net (code "32") (name "Net-(Q1-S)") (class "Default")
      (node (ref "Q1") (pin "2") (pinfunction "S_2") (pintype "passive"))
      (node (ref "SWITCH") (pin "P1A") (pinfunction "1.1_P1A") (pintype "passive"))
      (node (ref "SWITCH") (pin "P1B") (pinfunction "1.2_P1B") (pintype "passive"))
    )
    (net (code "33") (name "Net-(RFA-AGND)") (class "Default")
      (node (ref "CGA") (pin "1") (pinfunction "1_1") (pintype "passive"))
      (node (ref "RFA") (pin "11") (pinfunction "AGND_11") (pintype "power_in"))
    )
    (net (code "34") (name "Net-(RFA-ANT1)") (class "Default")
      (node (ref "RAA") (pin "2") (pinfunction "2_2") (pintype "passive"))
      (node (ref "RFA") (pin "3") (pinfunction "ANT1_3") (pintype "passive"))
    )
    (net (code "35") (name "Net-(RFA-ANT2)") (class "Default")
      (node (ref "CR1A") (pin "1") (pinfunction "1_1") (pintype "passive"))
      (node (ref "CR2A") (pin "1") (pinfunction "1_1") (pintype "passive"))
      (node (ref "RFA") (pin "6") (pinfunction "ANT2_6") (pintype "passive"))
    )
    (net (code "36") (name "Net-(RFA-CDEC_IN)") (class "Default")
      (node (ref "CD2A") (pin "1") (pinfunction "1_1") (pintype "passive"))
      (node (ref "RFA") (pin "10") (pinfunction "CDEC_IN_10") (pintype "input"))
    )
    (net (code "37") (name "Net-(RFA-CDEC_OUT)") (class "Default")
      (node (ref "CD2A") (pin "2") (pinfunction "2_2") (pintype "passive"))
      (node (ref "RFA") (pin "9") (pinfunction "CDEC_OUT_9") (pintype "output"))
    )
    (net (code "38") (name "Net-(RFA-DC2)") (class "Default")
      (node (ref "CD1A") (pin "1") (pinfunction "1_1") (pintype "passive"))
      (node (ref "RFA") (pin "16") (pinfunction "DC2_16") (pintype "passive"))
    )
    (net (code "39") (name "Net-(RFA-DMOD_IN)") (class "Default")
      (node (ref "CV1A") (pin "2") (pinfunction "2_2") (pintype "passive"))
      (node (ref "CV2A") (pin "1") (pinfunction "1_1") (pintype "passive"))
      (node (ref "RFA") (pin "8") (pinfunction "DMOD_IN_8") (pintype "input"))
    )
    (net (code "40") (name "Net-(RFA-FCAP)") (class "Default")
      (node (ref "CFA") (pin "1") (pinfunction "1_1") (pintype "passive"))
      (node (ref "RFA") (pin "15") (pinfunction "FCAP_15") (pintype "passive"))
    )
    (net (code "41") (name "Net-(RFB-AGND)") (class "Default")
      (node (ref "CGB") (pin "1") (pinfunction "1_1") (pintype "passive"))
      (node (ref "RFB") (pin "11") (pinfunction "AGND_11") (pintype "power_in"))
    )
    (net (code "42") (name "Net-(RFB-ANT1)") (class "Default")
      (node (ref "RAB") (pin "2") (pinfunction "2_2") (pintype "passive"))
      (node (ref "RFB") (pin "3") (pinfunction "ANT1_3") (pintype "passive"))
    )
    (net (code "43") (name "Net-(RFB-ANT2)") (class "Default")
      (node (ref "CR1B") (pin "1") (pinfunction "1_1") (pintype "passive"))
      (node (ref "CR2B") (pin "1") (pinfunction "1_1") (pintype "passive"))
      (node (ref "RFB") (pin "6") (pinfunction "ANT2_6") (pintype "passive"))
    )
    (net (code "44") (name "Net-(RFB-CDEC_IN)") (class "Default")
      (node (ref "CD2B") (pin "1") (pinfunction "1_1") (pintype "passive"))
      (node (ref "RFB") (pin "10") (pinfunction "CDEC_IN_10") (pintype "input"))
    )
    (net (code "45") (name "Net-(RFB-CDEC_OUT)") (class "Default")
      (node (ref "CD2B") (pin "2") (pinfunction "2_2") (pintype "passive"))
      (node (ref "RFB") (pin "9") (pinfunction "CDEC_OUT_9") (pintype "output"))
    )
    (net (code "46") (name "Net-(RFB-DC2)") (class "Default")
      (node (ref "CD1B") (pin "1") (pinfunction "1_1") (pintype "passive"))
      (node (ref "RFB") (pin "16") (pinfunction "DC2_16") (pintype "passive"))
    )
    (net (code "47") (name "Net-(RFB-DMOD_IN)") (class "Default")
      (node (ref "CV1B") (pin "2") (pinfunction "2_2") (pintype "passive"))
      (node (ref "CV2B") (pin "1") (pinfunction "1_1") (pintype "passive"))
      (node (ref "RFB") (pin "8") (pinfunction "DMOD_IN_8") (pintype "input"))
    )
    (net (code "48") (name "Net-(RFB-FCAP)") (class "Default")
      (node (ref "CFB") (pin "1") (pinfunction "1_1") (pintype "passive"))
      (node (ref "RFB") (pin "15") (pinfunction "FCAP_15") (pintype "passive"))
    )
    (net (code "49") (name "Net-(RTC-V_BAK)") (class "Default")
      (node (ref "R3") (pin "1") (pinfunction "1_1") (pintype "passive"))
      (node (ref "RTC") (pin "P$9") (pinfunction "V_BAK_P$9") (pintype "power_in"))
    )
    (net (code "50") (name "Net-(SD-VDD)") (class "Default")
      (node (ref "SD") (pin "4") (pinfunction "VDD_4") (pintype "power_in"))
      (node (ref "T_SD") (pin "3") (pinfunction "D_3") (pintype "passive"))
    )
    (net (code "51") (name "Net-(SWITCH-2.1)") (class "Default")
      (node (ref "F1") (pin "1") (pinfunction "1_1") (pintype "bidirectional"))
      (node (ref "SWITCH") (pin "P2A") (pinfunction "2.1_P2A") (pintype "passive"))
      (node (ref "SWITCH") (pin "P2B") (pinfunction "2.2_P2B") (pintype "passive"))
    )
    (net (code "52") (name "Net-(USB-MTN1)") (class "Default")
      (node (ref "L7") (pin "1") (pinfunction "1_1") (pintype "passive"))
      (node (ref "USB") (pin "MTN1") (pinfunction "MTN2_MTN1") (pintype "bidirectional"))
      (node (ref "USB") (pin "MTN2") (pinfunction "MTN3_MTN2") (pintype "bidirectional"))
      (node (ref "USB") (pin "MTN3") (pinfunction "MTN1_MTN3") (pintype "bidirectional"))
      (node (ref "USB") (pin "MTN4") (pinfunction "MTN4_MTN4") (pintype "bidirectional"))
    )
    (net (code "53") (name "PIN_D0{slash}RX") (class "Default")
      (node (ref "AT_SAM") (pin "25") (pinfunction "PB12(SER4:0)_25") (pintype "bidirectional"))
      (node (ref "HDR_IOL") (pin "1") (pinfunction "1_1") (pintype "passive"))
    )
    (net (code "54") (name "PIN_D1{slash}TX") (class "Default")
      (node (ref "AT_SAM") (pin "26") (pinfunction "PB13(AIN3/SER4:1)_26") (pintype "bidirectional"))
      (node (ref "HDR_IOL") (pin "2") (pinfunction "2_2") (pintype "passive"))
    )
    (net (code "55") (name "PIN_D2") (class "Default")
      (node (ref "AT_SAM") (pin "27") (pinfunction "PB14(SER4:2)_27") (pintype "bidirectional"))
      (node (ref "HDR_IOL") (pin "3") (pinfunction "3_3") (pintype "passive"))
    )
    (net (code "56") (name "PIN_D3") (class "Default")
      (node (ref "AT_SAM") (pin "28") (pinfunction "PB15(AIN3/SER4:3)_28") (pintype "bidirectional"))
      (node (ref "HDR_IOL") (pin "4") (pinfunction "4_4") (pintype "passive"))
    )
    (net (code "57") (name "PIN_D4") (class "Default")
      (node (ref "AT_SAM") (pin "23") (pinfunction "PB10(SER4:2)_23") (pintype "bidirectional"))
      (node (ref "HDR_IOL") (pin "5") (pinfunction "5_5") (pintype "passive"))
    )
    (net (code "58") (name "PIN_D5") (class "Default")
      (node (ref "AT_SAM") (pin "24") (pinfunction "PB11(SER4:3)_24") (pintype "bidirectional"))
      (node (ref "HDR_IOL") (pin "6") (pinfunction "6_6") (pintype "passive"))
    )
    (net (code "59") (name "PIN_D6") (class "Default")
      (node (ref "AT_SAM") (pin "29") (pinfunction "PA12(SER2:0+)_29") (pintype "bidirectional"))
      (node (ref "HDR_IOL") (pin "7") (pinfunction "7_7") (pintype "passive"))
    )
    (net (code "60") (name "PIN_D7") (class "Default")
      (node (ref "AT_SAM") (pin "30") (pinfunction "PA13(SER2:1+)_30") (pintype "bidirectional"))
      (node (ref "HDR_IOL") (pin "8") (pinfunction "8_8") (pintype "passive"))
    )
    (net (code "61") (name "PIN_D8") (class "Default")
      (node (ref "AT_SAM") (pin "31") (pinfunction "PA14(XIN/SER2:2+)_31") (pintype "bidirectional"))
      (node (ref "HDR_IOH") (pin "1") (pinfunction "1_1") (pintype "passive"))
    )
    (net (code "62") (name "PIN_D9") (class "Default")
      (node (ref "AT_SAM") (pin "32") (pinfunction "PA15(XOUT/SER2:3+)_32") (pintype "bidirectional"))
      (node (ref "HDR_IOH") (pin "2") (pinfunction "2_2") (pintype "passive"))
    )
    (net (code "63") (name "PIN_D10{slash}SS") (class "Default")
      (node (ref "AT_SAM") (pin "37") (pinfunction "PA18(SER1:2+)_37") (pintype "bidirectional"))
      (node (ref "HDR_IOH") (pin "3") (pinfunction "3_3") (pintype "passive"))
    )
    (net (code "64") (name "PIN_D11{slash}MOSI") (class "Default")
      (node (ref "AT_SAM") (pin "35") (pinfunction "PA16(I2C/SER1:0+)_35") (pintype "bidirectional"))
      (node (ref "HDR_IOH") (pin "4") (pinfunction "4_4") (pintype "passive"))
    )
    (net (code "65") (name "PIN_D12{slash}MISO") (class "Default")
      (node (ref "AT_SAM") (pin "38") (pinfunction "PA19(SER1:3+)_38") (pintype "bidirectional"))
      (node (ref "HDR_IOH") (pin "5") (pinfunction "5_5") (pintype "passive"))
    )
    (net (code "66") (name "PIN_D13{slash}SCK") (class "Default")
      (node (ref "AT_SAM") (pin "36") (pinfunction "PA17(I2C/SER1:1+)_36") (pintype "bidirectional"))
      (node (ref "HDR_IOH") (pin "6") (pinfunction "6_6") (pintype "passive"))
    )
    (net (code "67") (name "PIN_D14") (class "Default")
      (node (ref "AT_SAM") (pin "59") (pinfunction "PB30(SER5:0)_59") (pintype "bidirectional"))
      (node (ref "AUX_IO") (pin "6") (pinfunction "6_6") (pintype "passive"))
    )
    (net (code "68") (name "PIN_D15") (class "Default")
      (node (ref "AT_SAM") (pin "60") (pinfunction "PB31(SER5:1)_60") (pintype "bidirectional"))
      (node (ref "AUX_IO") (pin "5") (pinfunction "5_5") (pintype "passive"))
    )
    (net (code "69") (name "RESET") (class "Default")
      (node (ref "AT_SAM") (pin "52") (pinfunction "~{RESET}_52") (pintype "bidirectional"))
      (node (ref "CRST") (pin "1") (pinfunction "1_1") (pintype "passive"))
      (node (ref "HDR_POWER") (pin "3") (pinfunction "3_3") (pintype "passive"))
      (node (ref "ICSP10") (pin "10") (pinfunction "10_10") (pintype "passive"))
      (node (ref "R2") (pin "1") (pinfunction "1_1") (pintype "passive"))
    )
    (net (code "70") (name "RFID_IN1") (class "Default")
      (node (ref "AT_SAM") (pin "49") (pinfunction "PB22(SER5:2)_49") (pintype "bidirectional"))
      (node (ref "RFA") (pin "13") (pinfunction "DMOD_OUT_13") (pintype "output"))
    )
    (net (code "71") (name "RFID_IN2") (class "Default")
      (node (ref "AT_SAM") (pin "50") (pinfunction "PB23(SER5:3)_50") (pintype "bidirectional"))
      (node (ref "RFB") (pin "13") (pinfunction "DMOD_OUT_13") (pintype "output"))
    )
    (net (code "72") (name "RFID_STBY1") (class "Default")
      (node (ref "AT_SAM") (pin "39") (pinfunction "PB16(SER5:0)_39") (pintype "bidirectional"))
      (node (ref "RFA") (pin "14") (pinfunction "SHD_14") (pintype "input"))
    )
    (net (code "73") (name "RFID_STBY2") (class "Default")
      (node (ref "AT_SAM") (pin "40") (pinfunction "PB17(AIN3/SER5:1)_40") (pintype "bidirectional"))
      (node (ref "RFB") (pin "14") (pinfunction "SHD_14") (pintype "input"))
    )
    (net (code "74") (name "RST") (class "Default")
      (node (ref "D1") (pin "A") (pinfunction "A_A") (pintype "passive"))
      (node (ref "ICSP6") (pin "5") (pinfunction "5_5") (pintype "passive"))
      (node (ref "R2") (pin "2") (pinfunction "2_2") (pintype "passive"))
      (node (ref "R4") (pin "1") (pinfunction "1_1") (pintype "passive"))
      (node (ref "RESET") (pin "3") (pinfunction "3_3") (pintype "passive"))
      (node (ref "RESET") (pin "4") (pinfunction "4_4") (pintype "passive"))
    )
    (net (code "75") (name "SD_FET") (class "Default")
      (node (ref "AT_SAM") (pin "15") (pinfunction "PA06(AIN6/SER0:2/TC1:0)_15") (pintype "bidirectional"))
      (node (ref "SDPD") (pin "2") (pinfunction "2_2") (pintype "passive"))
      (node (ref "SDPU") (pin "1") (pinfunction "1_1") (pintype "passive"))
      (node (ref "T_SD") (pin "1") (pinfunction "G_1") (pintype "passive"))
    )
    (net (code "76") (name "SPI_MISO") (class "Default")
      (node (ref "AT_SAM") (pin "20") (pinfunction "PA11(AIN19/SER0:3+)_20") (pintype "bidirectional"))
      (node (ref "FLASH") (pin "8") (pinfunction "SO_8") (pintype "bidirectional"))
      (node (ref "ICSP6") (pin "1") (pinfunction "1_1") (pintype "passive"))
      (node (ref "SD") (pin "7") (pinfunction "DATA_OUT_7") (pintype "output"))
    )
    (net (code "77") (name "SPI_MOSI") (class "Default")
      (node (ref "AT_SAM") (pin "17") (pinfunction "PA08(I2C/AIN16/SER0:0+)_17") (pintype "bidirectional"))
      (node (ref "FLASH") (pin "1") (pinfunction "SI_1") (pintype "bidirectional"))
      (node (ref "ICSP6") (pin "4") (pinfunction "4_4") (pintype "passive"))
      (node (ref "SD") (pin "2") (pinfunction "DATA_IN_2") (pintype "input"))
    )
    (net (code "78") (name "SPI_SCK") (class "Default")
      (node (ref "AT_SAM") (pin "18") (pinfunction "PA09(I2C/AIN17/SER0:1+)_18") (pintype "bidirectional"))
      (node (ref "FLASH") (pin "2") (pinfunction "SCK_2") (pintype "bidirectional"))
      (node (ref "ICSP6") (pin "3") (pinfunction "3_3") (pintype "passive"))
      (node (ref "SD") (pin "5") (pinfunction "SCLK_5") (pintype "input"))
    )
    (net (code "79") (name "SWCLK") (class "Default")
      (node (ref "AT_SAM") (pin "57") (pinfunction "PA30(SWCLK/SER1:2+)_57") (pintype "bidirectional"))
      (node (ref "ICSP10") (pin "4") (pinfunction "4_4") (pintype "passive"))
    )
    (net (code "80") (name "SWDIO") (class "Default")
      (node (ref "AT_SAM") (pin "58") (pinfunction "PA31(SWDIO/SER1:3+)_58") (pintype "bidirectional"))
      (node (ref "ICSP10") (pin "2") (pinfunction "2_2") (pintype "passive"))
    )
    (net (code "81") (name "USB_N") (class "Default")
      (node (ref "AT_SAM") (pin "45") (pinfunction "PA24(SER3:2+)_45") (pintype "bidirectional"))
      (node (ref "USB") (pin "D-") (pinfunction "D-_D-") (pintype "bidirectional"))
    )
    (net (code "82") (name "USB_P") (class "Default")
      (node (ref "AT_SAM") (pin "46") (pinfunction "PA25(SER3:3+)_46") (pintype "bidirectional"))
      (node (ref "USB") (pin "D+") (pinfunction "D+_D+") (pintype "bidirectional"))
    )
    (net (code "83") (name "V_IN") (class "Default")
      (node (ref "C5V") (pin "1") (pinfunction "1_1") (pintype "passive"))
      (node (ref "CBLKA") (pin "1") (pinfunction "1_1") (pintype "passive"))
      (node (ref "CBLKB") (pin "1") (pinfunction "1_1") (pintype "passive"))
      (node (ref "CE1") (pin "+") (pinfunction "+_+") (pintype "passive"))
      (node (ref "CE2") (pin "+") (pinfunction "+_+") (pintype "passive"))
      (node (ref "CE3") (pin "+") (pinfunction "+_+") (pintype "passive"))
      (node (ref "F1") (pin "2") (pinfunction "2_2") (pintype "bidirectional"))
      (node (ref "HDR_POWER") (pin "5") (pinfunction "5_5") (pintype "passive"))
      (node (ref "HDR_POWER") (pin "8") (pinfunction "8_8") (pintype "passive"))
      (node (ref "ICSP6") (pin "2") (pinfunction "2_2") (pintype "passive"))
      (node (ref "RFA") (pin "4") (pinfunction "DVDD_4") (pintype "power_in"))
      (node (ref "RFA") (pin "7") (pinfunction "VDD_7") (pintype "power_in"))
      (node (ref "RFB") (pin "4") (pinfunction "DVDD_4") (pintype "power_in"))
      (node (ref "RFB") (pin "7") (pinfunction "VDD_7") (pintype "power_in"))
      (node (ref "VREG") (pin "1") (pinfunction "VIN_1") (pintype "power_in"))
      (node (ref "VREG") (pin "3") (pinfunction "EN_3") (pintype "input"))
    )
    (net (code "84") (name "XIN32") (class "Default")
      (node (ref "AT_SAM") (pin "1") (pinfunction "PA00(XIN32/SER1:0/TC2:0)_1") (pintype "bidirectional"))
      (node (ref "C9") (pin "2") (pinfunction "2_2") (pintype "passive"))
      (node (ref "Y4") (pin "P$1") (pinfunction "1_P$1") (pintype "bidirectional"))
    )
    (net (code "85") (name "XOUT32") (class "Default")
      (node (ref "AT_SAM") (pin "2") (pinfunction "PA01(XOUT32/SER1:1/TC2:1)_2") (pintype "bidirectional"))
      (node (ref "C10") (pin "2") (pinfunction "2_2") (pintype "passive"))
      (node (ref "Y4") (pin "P$2") (pinfunction "2_P$2") (pintype "bidirectional"))
    )
    (net (code "86") (name "XUSB") (class "Default")
      (node (ref "C7") (pin "1") (pinfunction "1_1") (pintype "passive"))
      (node (ref "SWITCH") (pin "P3A") (pinfunction "3.1_P3A") (pintype "passive"))
      (node (ref "SWITCH") (pin "P3B") (pinfunction "3.2_P3B") (pintype "passive"))
      (node (ref "USB") (pin "VBUS") (pinfunction "VBUS_VBUS") (pintype "bidirectional"))
    )
    (net (code "87") (name "unconnected-(AT_SAM-PA04(AIN4{slash}REFB{slash}SER0:0{slash}TC0:0)-Pad13)") (class "Default")
      (node (ref "AT_SAM") (pin "13") (pinfunction "PA04(AIN4/REFB/SER0:0/TC0:0)_13") (pintype "bidirectional"))
    )
    (net (code "88") (name "unconnected-(AT_SAM-PA07(AIN7{slash}SER0:3{slash}TC1:1)-Pad16)") (class "Default")
      (node (ref "AT_SAM") (pin "16") (pinfunction "PA07(AIN7/SER0:3/TC1:1)_16") (pintype "bidirectional"))
    )
    (net (code "89") (name "unconnected-(AT_SAM-PA10(AIN18{slash}SER0:2+)-Pad19)") (class "Default")
      (node (ref "AT_SAM") (pin "19") (pinfunction "PA10(AIN18/SER0:2+)_19") (pintype "bidirectional"))
    )
    (net (code "90") (name "unconnected-(AT_SAM-PB09(AIN3{slash}SER4:1)-Pad12)") (class "Default")
      (node (ref "AT_SAM") (pin "12") (pinfunction "PB09(AIN3/SER4:1)_12") (pintype "bidirectional"))
    )
    (net (code "91") (name "unconnected-(HDR_POWER-Pad1)") (class "Default")
      (node (ref "HDR_POWER") (pin "1") (pinfunction "1_1") (pintype "passive"))
    )
    (net (code "92") (name "unconnected-(ICSP10-Pad6)") (class "Default")
      (node (ref "ICSP10") (pin "6") (pinfunction "6_6") (pintype "passive"))
    )
    (net (code "93") (name "unconnected-(ICSP10-Pad7)") (class "Default")
      (node (ref "ICSP10") (pin "7") (pinfunction "7_7") (pintype "passive"))
    )
    (net (code "94") (name "unconnected-(ICSP10-Pad8)") (class "Default")
      (node (ref "ICSP10") (pin "8") (pinfunction "8_8") (pintype "passive"))
    )
    (net (code "95") (name "unconnected-(RFA-RDY{slash}CLK-Pad2)") (class "Default")
      (node (ref "RFA") (pin "2") (pinfunction "RDY/CLK_2") (pintype "output"))
    )
    (net (code "96") (name "unconnected-(RFB-RDY{slash}CLK-Pad2)") (class "Default")
      (node (ref "RFB") (pin "2") (pinfunction "RDY/CLK_2") (pintype "output"))
    )
    (net (code "97") (name "unconnected-(RTC-CLKOE-PadP$1)") (class "Default")
      (node (ref "RTC") (pin "P$1") (pinfunction "CLKOE_P$1") (pintype "bidirectional"))
    )
    (net (code "98") (name "unconnected-(RTC-NC-PadP$8)") (class "Default")
      (node (ref "RTC") (pin "P$8") (pinfunction "NC_P$8") (pintype "no_connect"))
    )
    (net (code "99") (name "unconnected-(RTC-NC-PadP$10)") (class "Default")
      (node (ref "RTC") (pin "P$10") (pinfunction "NC_P$10") (pintype "no_connect"))
    )
    (net (code "100") (name "unconnected-(SD-CARD_DETECT-PadCD)") (class "Default")
      (node (ref "SD") (pin "CD") (pinfunction "CARD_DETECT_CD") (pintype "passive"))
    )
    (net (code "101") (name "unconnected-(SD-DAT1-Pad8)") (class "Default")
      (node (ref "SD") (pin "8") (pinfunction "DAT1_8") (pintype "bidirectional"))
    )
    (net (code "102") (name "unconnected-(SD-DAT2-Pad9)") (class "Default")
      (node (ref "SD") (pin "9") (pinfunction "DAT2_9") (pintype "bidirectional"))
    )
    (net (code "103") (name "unconnected-(SD-WRITE_PROTECT-PadWP)") (class "Default")
      (node (ref "SD") (pin "WP") (pinfunction "WRITE_PROTECT_WP") (pintype "passive"))
    )
    (net (code "104") (name "unconnected-(USB-PadID)") (class "Default")
      (node (ref "USB") (pin "ID") (pinfunction "ID_ID") (pintype "bidirectional"))
    )
  )
)
